# Jafar_-_EasyEDA_-_Schematic_Export.net
KiCad netlist of a schematic drawn in EasyEDA
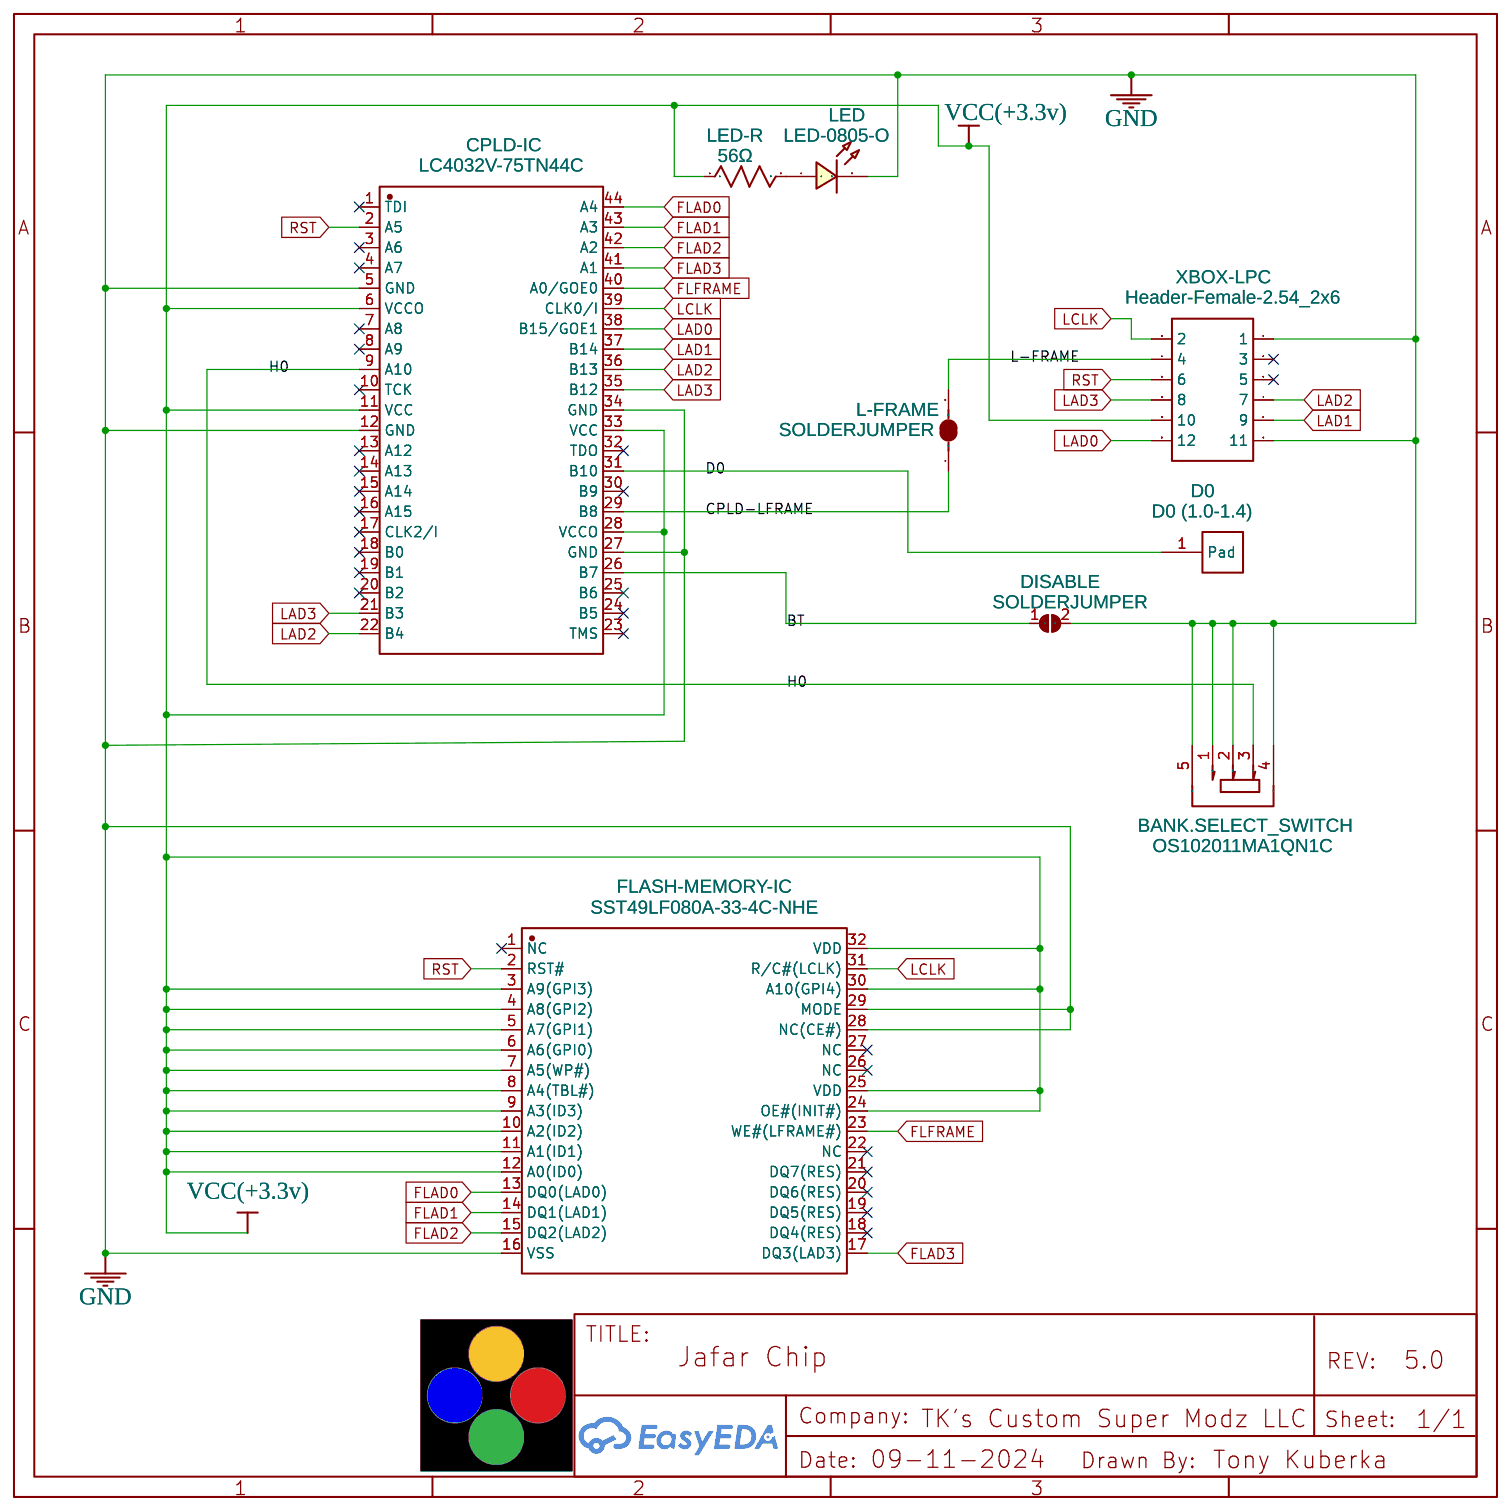
[diagram p0: schematic sheet]

(export (version "E")
  (design (tool "Eeschema 10.0.6"))
  (components
    (comp (ref "BANK.SELECT_SWITCH")
      (value "OS102011MA1QN1C")
      (fields (field (name "Manufacturer") "C&K"))
      (libsource (lib "") (part "OS102011MA1QN1C"))
    )
    (comp (ref "CPLD-IC")
      (value "LC4032V-75TN44C")
      (fields (field (name "Manufacturer") "LATTICE(莱迪思)"))
      (libsource (lib "") (part "LC4032V-75TN44C"))
    )
    (comp (ref "D0") (value "D0 (1.0-1.4)") (libsource (lib "") (part "SOLDER PAD")))
    (comp (ref "DISABLE")
      (value "SOLDERJUMPER")
      (fields (field (name "Manufacturer Part") "DNP"))
      (libsource (lib "") (part "Solder bridge"))
    )
    (comp (ref "FLASH-MEMORY-IC")
      (value "SST49LF080A-33-4C-NHE")
      (fields (field (name "Manufacturer") "MICROCHIP(美国微芯)"))
      (libsource (lib "") (part "SST49LF080A-33-4C-NHE"))
    )
    (comp (ref "L-FRAME") (value "SOLDERJUMPER") (libsource (lib "") (part "SOLDERJUMPER-OLDNC2")))
    (comp (ref "LED")
      (value "LED-0805-O")
      (fields
        (field (name "Manufacturer Part") "SZYY0805O")
        (field (name "Manufacturer") "Yongyu Photoelectric")
      )
      (libsource (lib "") (part "LED-0805-ORANGE"))
    )
    (comp (ref "LED-R") (value "56Ω") (libsource (lib "") (part "R_0805_US")))
    (comp (ref "XBOX-LPC")
      (value "Header-Female-2.54_2x6")
      (fields (field (name "Manufacturer Part") "2.54-2*6P母") (field (name "Manufacturer") "BOOMELE(博穆精密)"))
      (libsource (lib "") (part "Header-Female-2.54_2x6"))
    )
  )
  (nets
    (net (code "1") (name "/BT") (class "Default")
      (node (ref "CPLD-IC") (pin "26") (pinfunction "B7_26") (pintype "unspecified"))
      (node (ref "DISABLE") (pin "1") (pinfunction "A_1") (pintype "unspecified"))
    )
    (net (code "2") (name "/CPLD-LFRAME") (class "Default")
      (node (ref "CPLD-IC") (pin "29") (pinfunction "B8_29") (pintype "unspecified"))
      (node (ref "L-FRAME") (pin "1") (pinfunction "1_1") (pintype "unspecified"))
    )
    (net (code "3") (name "/D0") (class "Default")
      (node (ref "CPLD-IC") (pin "31") (pinfunction "B10_31") (pintype "unspecified"))
      (node (ref "D0") (pin "1") (pinfunction "Pad_1") (pintype "unspecified"))
    )
    (net (code "4") (name "/H0") (class "Default")
      (node (ref "BANK.SELECT_SWITCH") (pin "3") (pinfunction "3_3") (pintype "unspecified"))
      (node (ref "CPLD-IC") (pin "9") (pinfunction "A10_9") (pintype "unspecified"))
    )
    (net (code "5") (name "/L-FRAME") (class "Default")
      (node (ref "L-FRAME") (pin "2") (pinfunction "2_2") (pintype "unspecified"))
      (node (ref "XBOX-LPC") (pin "4") (pinfunction "4_4") (pintype "input"))
    )
    (net (code "6") (name "FLAD0") (class "Default")
      (node (ref "CPLD-IC") (pin "44") (pinfunction "A4_44") (pintype "unspecified"))
      (node (ref "FLASH-MEMORY-IC") (pin "13") (pinfunction "DQ0(LAD0)_13") (pintype "unspecified"))
    )
    (net (code "7") (name "FLAD1") (class "Default")
      (node (ref "CPLD-IC") (pin "43") (pinfunction "A3_43") (pintype "unspecified"))
      (node (ref "FLASH-MEMORY-IC") (pin "14") (pinfunction "DQ1(LAD1)_14") (pintype "unspecified"))
    )
    (net (code "8") (name "FLAD2") (class "Default")
      (node (ref "CPLD-IC") (pin "42") (pinfunction "A2_42") (pintype "unspecified"))
      (node (ref "FLASH-MEMORY-IC") (pin "15") (pinfunction "DQ2(LAD2)_15") (pintype "unspecified"))
    )
    (net (code "9") (name "FLAD3") (class "Default")
      (node (ref "CPLD-IC") (pin "41") (pinfunction "A1_41") (pintype "unspecified"))
      (node (ref "FLASH-MEMORY-IC") (pin "17") (pinfunction "DQ3(LAD3)_17") (pintype "unspecified"))
    )
    (net (code "10") (name "FLFRAME") (class "Default")
      (node (ref "CPLD-IC") (pin "40") (pinfunction "A0/GOE0_40") (pintype "unspecified"))
      (node (ref "FLASH-MEMORY-IC") (pin "23") (pinfunction "WE#(LFRAME#)_23") (pintype "unspecified"))
    )
    (net (code "11") (name "GND") (class "Default")
      (node (ref "BANK.SELECT_SWITCH") (pin "1") (pinfunction "1_1") (pintype "unspecified"))
      (node (ref "BANK.SELECT_SWITCH") (pin "2") (pinfunction "2_2") (pintype "unspecified"))
      (node (ref "BANK.SELECT_SWITCH") (pin "4") (pinfunction "4_4") (pintype "unspecified"))
      (node (ref "BANK.SELECT_SWITCH") (pin "5") (pinfunction "5_5") (pintype "unspecified"))
      (node (ref "CPLD-IC") (pin "12") (pinfunction "GND_12") (pintype "unspecified"))
      (node (ref "CPLD-IC") (pin "27") (pinfunction "GND_27") (pintype "unspecified"))
      (node (ref "CPLD-IC") (pin "34") (pinfunction "GND_34") (pintype "unspecified"))
      (node (ref "CPLD-IC") (pin "5") (pinfunction "GND_5") (pintype "unspecified"))
      (node (ref "DISABLE") (pin "2") (pinfunction "B_2") (pintype "unspecified"))
      (node (ref "FLASH-MEMORY-IC") (pin "16") (pinfunction "VSS_16") (pintype "unspecified"))
      (node (ref "FLASH-MEMORY-IC") (pin "28") (pinfunction "NC(CE#)_28") (pintype "unspecified"))
      (node (ref "FLASH-MEMORY-IC") (pin "29") (pinfunction "MODE_29") (pintype "unspecified"))
      (node (ref "LED") (pin "2") (pinfunction "2_2") (pintype "unspecified"))
      (node (ref "XBOX-LPC") (pin "1") (pinfunction "1_1") (pintype "input"))
      (node (ref "XBOX-LPC") (pin "11") (pinfunction "11_11") (pintype "input"))
    )
    (net (code "12") (name "LAD0") (class "Default")
      (node (ref "CPLD-IC") (pin "38") (pinfunction "B15/GOE1_38") (pintype "unspecified"))
      (node (ref "XBOX-LPC") (pin "12") (pinfunction "12_12") (pintype "input"))
    )
    (net (code "13") (name "LAD1") (class "Default")
      (node (ref "CPLD-IC") (pin "37") (pinfunction "B14_37") (pintype "unspecified"))
      (node (ref "XBOX-LPC") (pin "9") (pinfunction "9_9") (pintype "input"))
    )
    (net (code "14") (name "LAD2") (class "Default")
      (node (ref "CPLD-IC") (pin "22") (pinfunction "B4_22") (pintype "unspecified"))
      (node (ref "CPLD-IC") (pin "36") (pinfunction "B13_36") (pintype "unspecified"))
      (node (ref "XBOX-LPC") (pin "7") (pinfunction "7_7") (pintype "input"))
    )
    (net (code "15") (name "LAD3") (class "Default")
      (node (ref "CPLD-IC") (pin "21") (pinfunction "B3_21") (pintype "unspecified"))
      (node (ref "CPLD-IC") (pin "35") (pinfunction "B12_35") (pintype "unspecified"))
      (node (ref "XBOX-LPC") (pin "8") (pinfunction "8_8") (pintype "input"))
    )
    (net (code "16") (name "LCLK") (class "Default")
      (node (ref "CPLD-IC") (pin "39") (pinfunction "CLK0/I_39") (pintype "unspecified"))
      (node (ref "FLASH-MEMORY-IC") (pin "31") (pinfunction "R/C#(LCLK)_31") (pintype "unspecified"))
      (node (ref "XBOX-LPC") (pin "2") (pinfunction "2_2") (pintype "input"))
    )
    (net (code "17") (name "Net-(LED-Pad1)") (class "Default")
      (node (ref "LED") (pin "1") (pinfunction "1_1") (pintype "unspecified"))
      (node (ref "LED-R") (pin "2") (pinfunction "2_2") (pintype "unspecified"))
    )
    (net (code "18") (name "RST") (class "Default")
      (node (ref "CPLD-IC") (pin "2") (pinfunction "A5_2") (pintype "unspecified"))
      (node (ref "FLASH-MEMORY-IC") (pin "2") (pinfunction "RST#_2") (pintype "unspecified"))
      (node (ref "XBOX-LPC") (pin "6") (pinfunction "6_6") (pintype "input"))
    )
    (net (code "19") (name "VCC(+3.3v)") (class "Default")
      (node (ref "CPLD-IC") (pin "11") (pinfunction "VCC_11") (pintype "unspecified"))
      (node (ref "CPLD-IC") (pin "28") (pinfunction "VCCO_28") (pintype "unspecified"))
      (node (ref "CPLD-IC") (pin "33") (pinfunction "VCC_33") (pintype "unspecified"))
      (node (ref "CPLD-IC") (pin "6") (pinfunction "VCCO_6") (pintype "unspecified"))
      (node (ref "FLASH-MEMORY-IC") (pin "10") (pinfunction "A2(ID2)_10") (pintype "unspecified"))
      (node (ref "FLASH-MEMORY-IC") (pin "11") (pinfunction "A1(ID1)_11") (pintype "unspecified"))
      (node (ref "FLASH-MEMORY-IC") (pin "12") (pinfunction "A0(ID0)_12") (pintype "unspecified"))
      (node (ref "FLASH-MEMORY-IC") (pin "24") (pinfunction "OE#(INIT#)_24") (pintype "unspecified"))
      (node (ref "FLASH-MEMORY-IC") (pin "25") (pinfunction "VDD_25") (pintype "unspecified"))
      (node (ref "FLASH-MEMORY-IC") (pin "3") (pinfunction "A9(GPI3)_3") (pintype "unspecified"))
      (node (ref "FLASH-MEMORY-IC") (pin "30") (pinfunction "A10(GPI4)_30") (pintype "unspecified"))
      (node (ref "FLASH-MEMORY-IC") (pin "32") (pinfunction "VDD_32") (pintype "unspecified"))
      (node (ref "FLASH-MEMORY-IC") (pin "4") (pinfunction "A8(GPI2)_4") (pintype "unspecified"))
      (node (ref "FLASH-MEMORY-IC") (pin "5") (pinfunction "A7(GPI1)_5") (pintype "unspecified"))
      (node (ref "FLASH-MEMORY-IC") (pin "6") (pinfunction "A6(GPI0)_6") (pintype "unspecified"))
      (node (ref "FLASH-MEMORY-IC") (pin "7") (pinfunction "A5(WP#)_7") (pintype "unspecified"))
      (node (ref "FLASH-MEMORY-IC") (pin "8") (pinfunction "A4(TBL#)_8") (pintype "unspecified"))
      (node (ref "FLASH-MEMORY-IC") (pin "9") (pinfunction "A3(ID3)_9") (pintype "unspecified"))
      (node (ref "LED-R") (pin "1") (pinfunction "1_1") (pintype "unspecified"))
      (node (ref "XBOX-LPC") (pin "10") (pinfunction "10_10") (pintype "input"))
    )
    (net (code "20") (name "unconnected-(CPLD-IC-A6-Pad3)") (class "Default")
      (node (ref "CPLD-IC") (pin "3") (pinfunction "A6_3") (pintype "unspecified+no_connect"))
    )
    (net (code "21") (name "unconnected-(CPLD-IC-A7-Pad4)") (class "Default")
      (node (ref "CPLD-IC") (pin "4") (pinfunction "A7_4") (pintype "unspecified+no_connect"))
    )
    (net (code "22") (name "unconnected-(CPLD-IC-A8-Pad7)") (class "Default")
      (node (ref "CPLD-IC") (pin "7") (pinfunction "A8_7") (pintype "unspecified+no_connect"))
    )
    (net (code "23") (name "unconnected-(CPLD-IC-A9-Pad8)") (class "Default")
      (node (ref "CPLD-IC") (pin "8") (pinfunction "A9_8") (pintype "unspecified+no_connect"))
    )
    (net (code "24") (name "unconnected-(CPLD-IC-A12-Pad13)") (class "Default")
      (node (ref "CPLD-IC") (pin "13") (pinfunction "A12_13") (pintype "unspecified+no_connect"))
    )
    (net (code "25") (name "unconnected-(CPLD-IC-A13-Pad14)") (class "Default")
      (node (ref "CPLD-IC") (pin "14") (pinfunction "A13_14") (pintype "unspecified+no_connect"))
    )
    (net (code "26") (name "unconnected-(CPLD-IC-A14-Pad15)") (class "Default")
      (node (ref "CPLD-IC") (pin "15") (pinfunction "A14_15") (pintype "unspecified+no_connect"))
    )
    (net (code "27") (name "unconnected-(CPLD-IC-A15-Pad16)") (class "Default")
      (node (ref "CPLD-IC") (pin "16") (pinfunction "A15_16") (pintype "unspecified+no_connect"))
    )
    (net (code "28") (name "unconnected-(CPLD-IC-B0-Pad18)") (class "Default")
      (node (ref "CPLD-IC") (pin "18") (pinfunction "B0_18") (pintype "unspecified+no_connect"))
    )
    (net (code "29") (name "unconnected-(CPLD-IC-B1-Pad19)") (class "Default")
      (node (ref "CPLD-IC") (pin "19") (pinfunction "B1_19") (pintype "unspecified+no_connect"))
    )
    (net (code "30") (name "unconnected-(CPLD-IC-B2-Pad20)") (class "Default")
      (node (ref "CPLD-IC") (pin "20") (pinfunction "B2_20") (pintype "unspecified+no_connect"))
    )
    (net (code "31") (name "unconnected-(CPLD-IC-B5-Pad24)") (class "Default")
      (node (ref "CPLD-IC") (pin "24") (pinfunction "B5_24") (pintype "unspecified+no_connect"))
    )
    (net (code "32") (name "unconnected-(CPLD-IC-B6-Pad25)") (class "Default")
      (node (ref "CPLD-IC") (pin "25") (pinfunction "B6_25") (pintype "unspecified+no_connect"))
    )
    (net (code "33") (name "unconnected-(CPLD-IC-B9-Pad30)") (class "Default")
      (node (ref "CPLD-IC") (pin "30") (pinfunction "B9_30") (pintype "unspecified+no_connect"))
    )
    (net (code "34") (name "unconnected-(CPLD-IC-CLK2{slash}I-Pad17)") (class "Default")
      (node (ref "CPLD-IC") (pin "17") (pinfunction "CLK2/I_17") (pintype "unspecified+no_connect"))
    )
    (net (code "35") (name "unconnected-(CPLD-IC-TCK-Pad10)") (class "Default")
      (node (ref "CPLD-IC") (pin "10") (pinfunction "TCK_10") (pintype "unspecified+no_connect"))
    )
    (net (code "36") (name "unconnected-(CPLD-IC-TDI-Pad1)") (class "Default")
      (node (ref "CPLD-IC") (pin "1") (pinfunction "TDI_1") (pintype "unspecified+no_connect"))
    )
    (net (code "37") (name "unconnected-(CPLD-IC-TDO-Pad32)") (class "Default")
      (node (ref "CPLD-IC") (pin "32") (pinfunction "TDO_32") (pintype "unspecified+no_connect"))
    )
    (net (code "38") (name "unconnected-(CPLD-IC-TMS-Pad23)") (class "Default")
      (node (ref "CPLD-IC") (pin "23") (pinfunction "TMS_23") (pintype "unspecified+no_connect"))
    )
    (net (code "39") (name "unconnected-(FLASH-MEMORY-IC-DQ4(RES)-Pad18)") (class "Default")
      (node (ref "FLASH-MEMORY-IC") (pin "18") (pinfunction "DQ4(RES)_18") (pintype "unspecified+no_connect"))
    )
    (net (code "40") (name "unconnected-(FLASH-MEMORY-IC-DQ5(RES)-Pad19)") (class "Default")
      (node (ref "FLASH-MEMORY-IC") (pin "19") (pinfunction "DQ5(RES)_19") (pintype "unspecified+no_connect"))
    )
    (net (code "41") (name "unconnected-(FLASH-MEMORY-IC-DQ6(RES)-Pad20)") (class "Default")
      (node (ref "FLASH-MEMORY-IC") (pin "20") (pinfunction "DQ6(RES)_20") (pintype "unspecified+no_connect"))
    )
    (net (code "42") (name "unconnected-(FLASH-MEMORY-IC-DQ7(RES)-Pad21)") (class "Default")
      (node (ref "FLASH-MEMORY-IC") (pin "21") (pinfunction "DQ7(RES)_21") (pintype "unspecified+no_connect"))
    )
    (net (code "43") (name "unconnected-(FLASH-MEMORY-IC-NC-Pad1)") (class "Default")
      (node (ref "FLASH-MEMORY-IC") (pin "1") (pinfunction "NC_1") (pintype "unspecified+no_connect"))
    )
    (net (code "44") (name "unconnected-(FLASH-MEMORY-IC-NC-Pad22)") (class "Default")
      (node (ref "FLASH-MEMORY-IC") (pin "22") (pinfunction "NC_22") (pintype "unspecified+no_connect"))
    )
    (net (code "45") (name "unconnected-(FLASH-MEMORY-IC-NC-Pad26)") (class "Default")
      (node (ref "FLASH-MEMORY-IC") (pin "26") (pinfunction "NC_26") (pintype "unspecified+no_connect"))
    )
    (net (code "46") (name "unconnected-(FLASH-MEMORY-IC-NC-Pad27)") (class "Default")
      (node (ref "FLASH-MEMORY-IC") (pin "27") (pinfunction "NC_27") (pintype "unspecified+no_connect"))
    )
    (net (code "47") (name "unconnected-(XBOX-LPC-Pad3)") (class "Default")
      (node (ref "XBOX-LPC") (pin "3") (pinfunction "3_3") (pintype "input+no_connect"))
    )
    (net (code "48") (name "unconnected-(XBOX-LPC-Pad5)") (class "Default")
      (node (ref "XBOX-LPC") (pin "5") (pinfunction "5_5") (pintype "input+no_connect"))
    )
  )
)
